# childboard_relay_v1.net
KiCad netlist of a schematic drawn in EAGLE
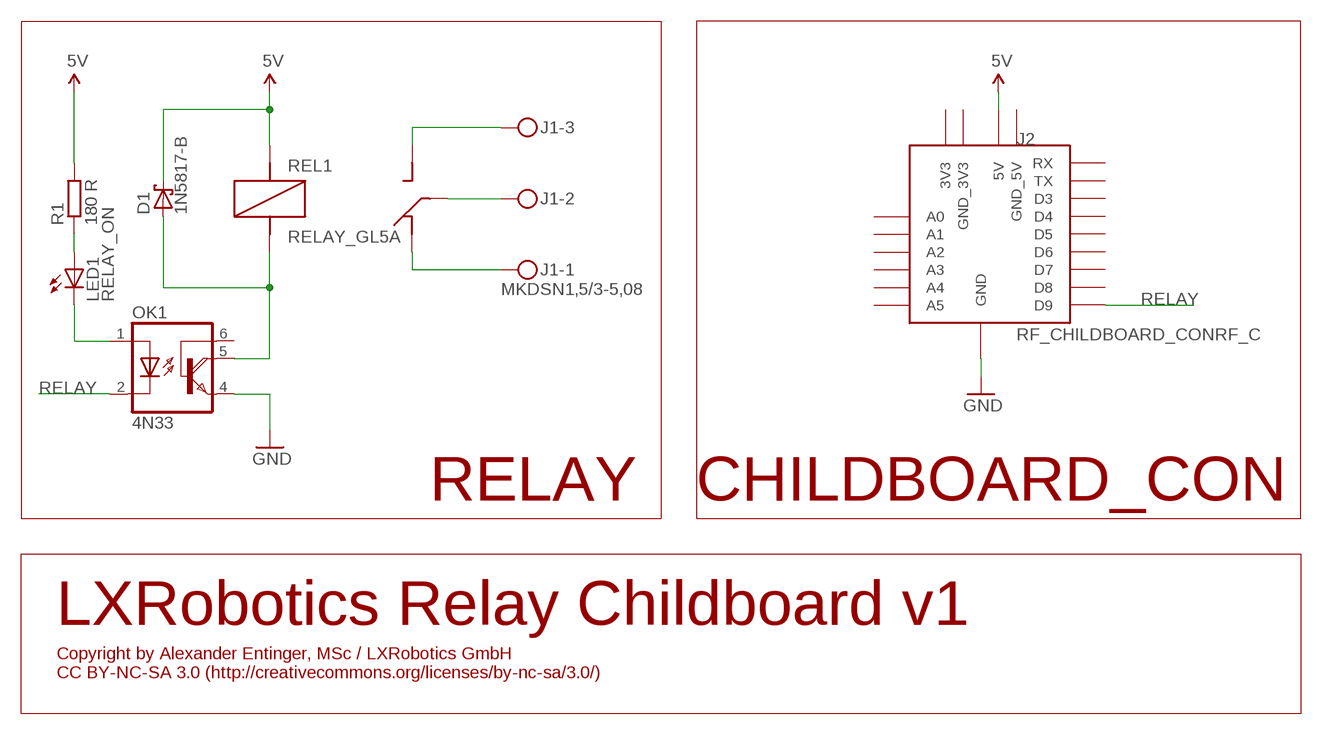
[diagram p0: schematic, sheet 1]

(export (version "E")
  (design (tool "Eeschema 10.0.6"))
  (components
    (comp (ref "D1")
      (value "1N5817-B")
      (footprint "eagle-import:DO41-7.6")
      (libsource (lib "eagle-import") (part "1N5817-B"))
    )
    (comp (ref "J1")
      (value "MKDSN1,5/3-5,08")
      (footprint "eagle-import:MKDSN1,5_3-5,08")
      (fields (field (name "MPN") "SMKDSN1,5/3-5,08"))
      (libsource (lib "eagle-import") (part "MKDSN1,5/3-5,08"))
    )
    (comp (ref "J2")
      (value "RF_CHILDBOARD_CONRF_C")
      (footprint "eagle-import:RF_CHILDBOARD_CON")
      (libsource (lib "eagle-import") (part "RF_CHILDBOARD_CONRF_C"))
    )
    (comp (ref "LED1")
      (value "RELAY_ON")
      (footprint "eagle-import:LED5MM")
      (libsource (lib "eagle-import") (part "LED5MM"))
    )
    (comp (ref "OK1")
      (value "4N33")
      (footprint "eagle-import:DIL06")
      (fields (field (name "MF") "VISHAY/TELEFUNKEN"))
      (libsource (lib "eagle-import") (part "4N33"))
    )
    (comp (ref "R1")
      (value "180 R")
      (footprint "eagle-import:0204_7")
      (libsource (lib "eagle-import") (part "R-EU_0204/7"))
    )
    (comp (ref "REL1")
      (value "RELAY_GL5A")
      (footprint "eagle-import:RELAY_GL5A")
      (libsource (lib "eagle-import") (part "RELAY_GL5A"))
    )
  )
  (nets
    (net (code "1") (name "/RELAY") (class "Default")
      (node (ref "J2") (pin "D9") (pinfunction "D9_D9") (pintype "bidirectional"))
      (node (ref "OK1") (pin "2") (pinfunction "C_2") (pintype "passive"))
    )
    (net (code "2") (name "5V") (class "Default")
      (node (ref "D1") (pin "C") (pinfunction "C_C") (pintype "passive"))
      (node (ref "J2") (pin "5V") (pinfunction "5V_5V") (pintype "bidirectional"))
      (node (ref "R1") (pin "2") (pinfunction "2_2") (pintype "passive"))
      (node (ref "REL1") (pin "R2") (pinfunction "R2_COIL1_R2") (pintype "bidirectional"))
    )
    (net (code "3") (name "GND") (class "Default")
      (node (ref "J2") (pin "GND_") (pinfunction "GND_GND_") (pintype "bidirectional"))
      (node (ref "OK1") (pin "4") (pinfunction "E_4") (pintype "passive"))
    )
    (net (code "4") (name "Net-(J1A-KL)") (class "Default")
      (node (ref "J1") (pin "1") (pinfunction "KL_1") (pintype "passive"))
      (node (ref "REL1") (pin "R4") (pinfunction "R4_SW_R4") (pintype "bidirectional"))
    )
    (net (code "5") (name "Net-(J1B-KL)") (class "Default")
      (node (ref "J1") (pin "2") (pinfunction "KL_2") (pintype "passive"))
      (node (ref "REL1") (pin "R1") (pinfunction "R1_COMMON_R1") (pintype "bidirectional"))
    )
    (net (code "6") (name "Net-(J1C-KL)") (class "Default")
      (node (ref "J1") (pin "3") (pinfunction "KL_3") (pintype "passive"))
      (node (ref "REL1") (pin "R3") (pinfunction "R3_SW_R3") (pintype "bidirectional"))
    )
    (net (code "7") (name "Net-(LED1-C)") (class "Default")
      (node (ref "LED1") (pin "K") (pinfunction "C_K") (pintype "passive"))
      (node (ref "OK1") (pin "1") (pinfunction "A_1") (pintype "passive"))
    )
    (net (code "8") (name "Net-(LED1-PadA)") (class "Default")
      (node (ref "LED1") (pin "A") (pinfunction "A_A") (pintype "passive"))
      (node (ref "R1") (pin "1") (pinfunction "1_1") (pintype "passive"))
    )
    (net (code "9") (name "Net-(OK1-COL)") (class "Default")
      (node (ref "D1") (pin "A") (pinfunction "A_A") (pintype "passive"))
      (node (ref "OK1") (pin "5") (pinfunction "COL_5") (pintype "passive"))
      (node (ref "REL1") (pin "R5") (pinfunction "R5_COIL2_R5") (pintype "bidirectional"))
    )
    (net (code "10") (name "unconnected-(J2-Pad3V3)") (class "Default")
      (node (ref "J2") (pin "3V3") (pinfunction "3V3_3V3") (pintype "bidirectional"))
    )
    (net (code "11") (name "unconnected-(J2-PadA0)") (class "Default")
      (node (ref "J2") (pin "A0") (pinfunction "A0_A0") (pintype "bidirectional"))
    )
    (net (code "12") (name "unconnected-(J2-PadA1)") (class "Default")
      (node (ref "J2") (pin "A1") (pinfunction "A1_A1") (pintype "bidirectional"))
    )
    (net (code "13") (name "unconnected-(J2-PadA2)") (class "Default")
      (node (ref "J2") (pin "A2") (pinfunction "A2_A2") (pintype "bidirectional"))
    )
    (net (code "14") (name "unconnected-(J2-PadA3)") (class "Default")
      (node (ref "J2") (pin "A3") (pinfunction "A3_A3") (pintype "bidirectional"))
    )
    (net (code "15") (name "unconnected-(J2-PadA4)") (class "Default")
      (node (ref "J2") (pin "A4") (pinfunction "A4_A4") (pintype "bidirectional"))
    )
    (net (code "16") (name "unconnected-(J2-PadA5)") (class "Default")
      (node (ref "J2") (pin "A5") (pinfunction "A5_A5") (pintype "bidirectional"))
    )
    (net (code "17") (name "unconnected-(J2-PadD3)") (class "Default")
      (node (ref "J2") (pin "D3") (pinfunction "D3_D3") (pintype "bidirectional"))
    )
    (net (code "18") (name "unconnected-(J2-PadD4)") (class "Default")
      (node (ref "J2") (pin "D4") (pinfunction "D4_D4") (pintype "bidirectional"))
    )
    (net (code "19") (name "unconnected-(J2-PadD5)") (class "Default")
      (node (ref "J2") (pin "D5") (pinfunction "D5_D5") (pintype "bidirectional"))
    )
    (net (code "20") (name "unconnected-(J2-PadD6)") (class "Default")
      (node (ref "J2") (pin "D6") (pinfunction "D6_D6") (pintype "bidirectional"))
    )
    (net (code "21") (name "unconnected-(J2-PadD7)") (class "Default")
      (node (ref "J2") (pin "D7") (pinfunction "D7_D7") (pintype "bidirectional"))
    )
    (net (code "22") (name "unconnected-(J2-PadD8)") (class "Default")
      (node (ref "J2") (pin "D8") (pinfunction "D8_D8") (pintype "bidirectional"))
    )
    (net (code "23") (name "unconnected-(J2-PadGND_3V3)") (class "Default")
      (node (ref "J2") (pin "GND_3V3") (pinfunction "GND_3V3_GND_3V3") (pintype "bidirectional"))
    )
    (net (code "24") (name "unconnected-(J2-PadGND_5V)") (class "Default")
      (node (ref "J2") (pin "GND_5V") (pinfunction "GND_5V_GND_5V") (pintype "bidirectional"))
    )
    (net (code "25") (name "unconnected-(J2-PadRX)") (class "Default")
      (node (ref "J2") (pin "RX") (pinfunction "RX_RX") (pintype "bidirectional"))
    )
    (net (code "26") (name "unconnected-(J2-PadTX)") (class "Default")
      (node (ref "J2") (pin "TX") (pinfunction "TX_TX") (pintype "bidirectional"))
    )
    (net (code "27") (name "unconnected-(OK1-B-Pad6)") (class "Default")
      (node (ref "OK1") (pin "6") (pinfunction "B_6") (pintype "passive"))
    )
  )
)
